# kit_calibration_VNA.net
KiCad netlist of a schematic drawn in EAGLE
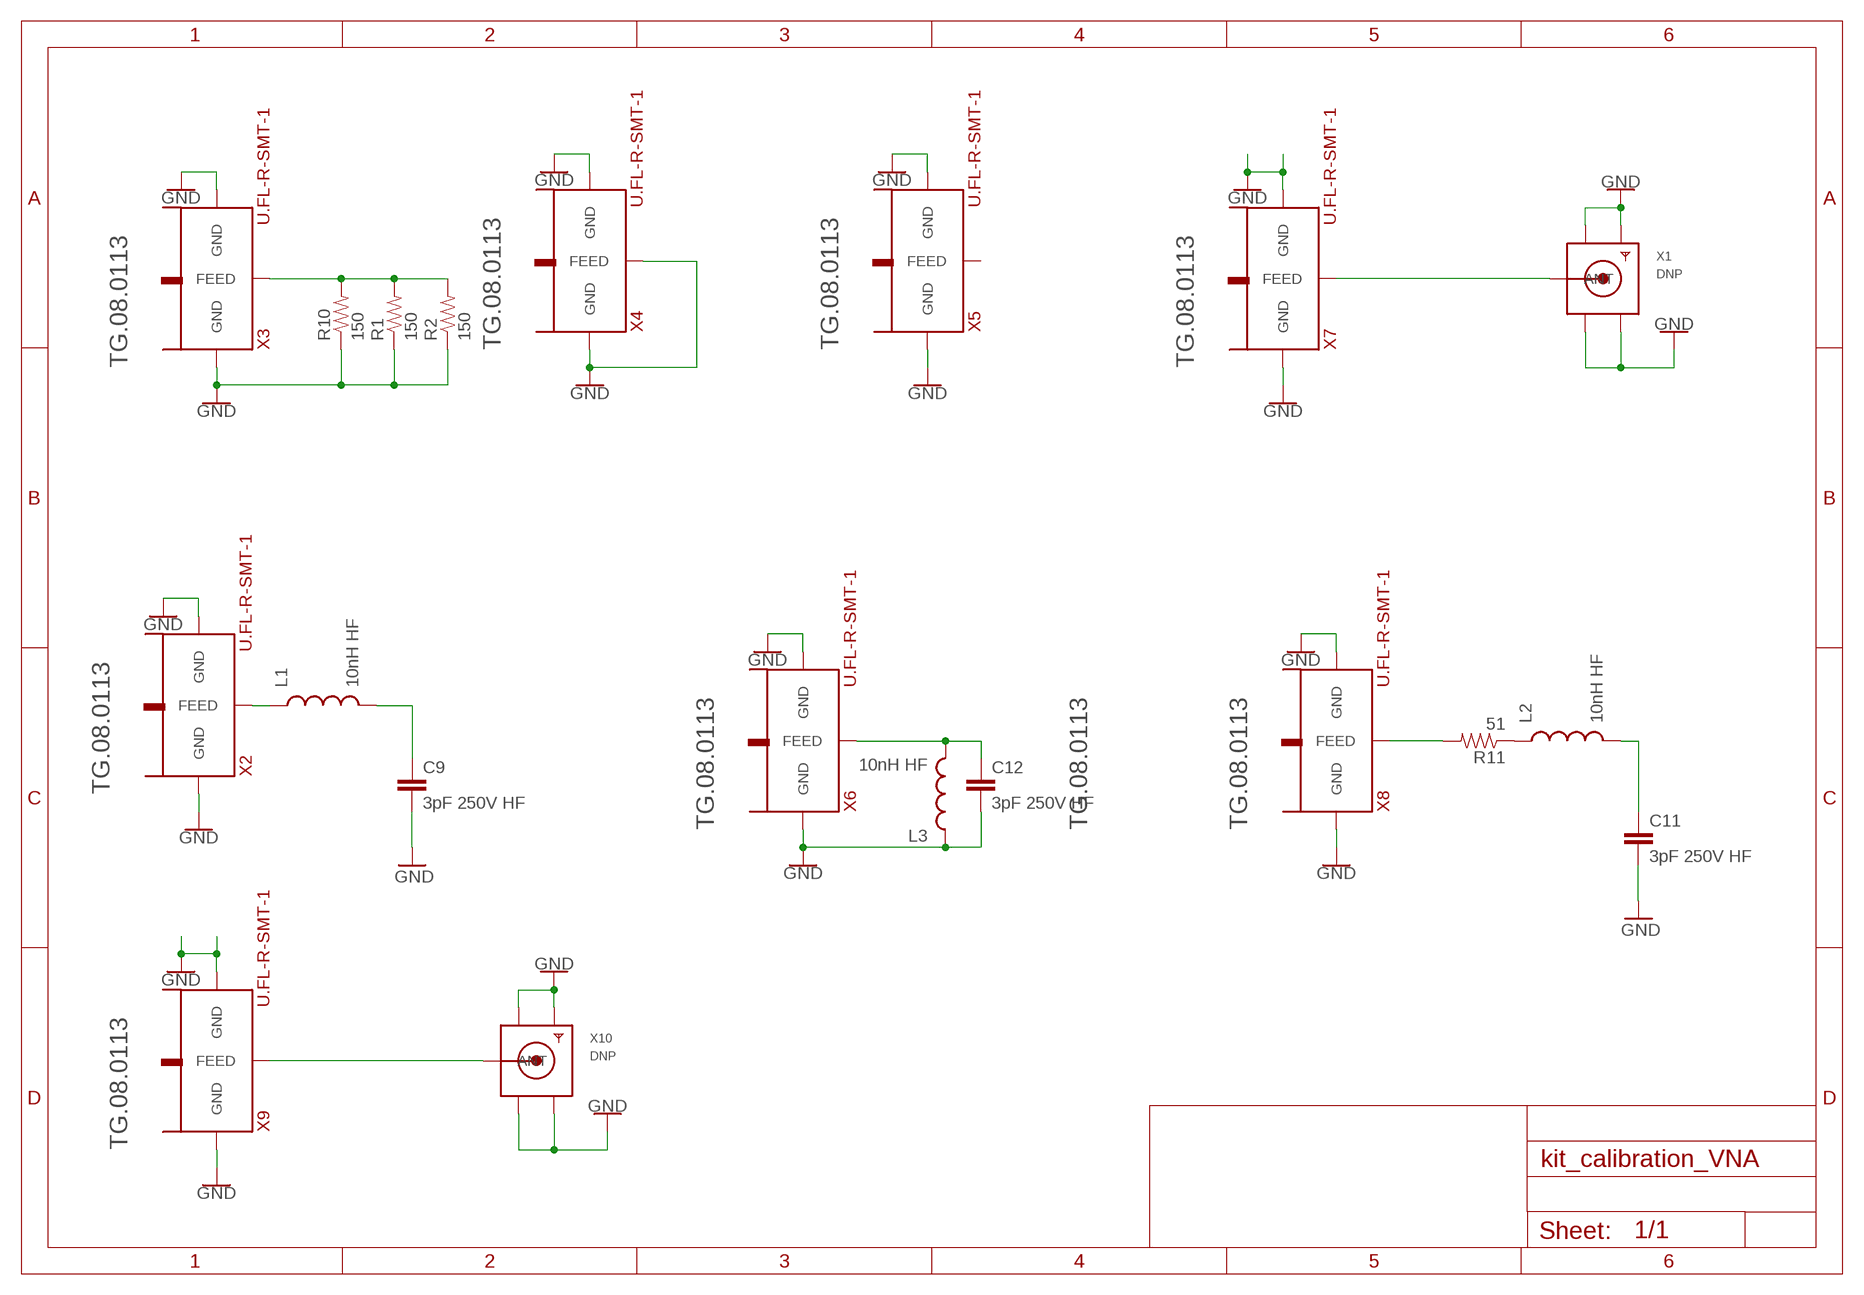
[diagram p0: schematic, sheet 1]

(export (version "E")
  (design (tool "Eeschema 10.0.6"))
  (components
    (comp (ref "C9")
      (value "3pF 250V HF")
      (footprint "eagle-import:0603-CAP")
      (libsource (lib "eagle-import") (part "CAP0603-CAP"))
    )
    (comp (ref "C11")
      (value "3pF 250V HF")
      (footprint "eagle-import:0603-CAP")
      (libsource (lib "eagle-import") (part "CAP0603-CAP"))
    )
    (comp (ref "C12")
      (value "3pF 250V HF")
      (footprint "eagle-import:0603-CAP")
      (libsource (lib "eagle-import") (part "CAP0603-CAP"))
    )
    (comp (ref "L1")
      (value "10nH HF")
      (footprint "eagle-import:0603")
      (libsource (lib "eagle-import") (part "INDUCTOR0603"))
    )
    (comp (ref "L2")
      (value "10nH HF")
      (footprint "eagle-import:0603")
      (libsource (lib "eagle-import") (part "INDUCTOR0603"))
    )
    (comp (ref "L3")
      (value "10nH HF")
      (footprint "eagle-import:0603")
      (libsource (lib "eagle-import") (part "INDUCTOR0603"))
    )
    (comp (ref "R1")
      (value "150")
      (footprint "eagle-import:0603-RES")
      (libsource (lib "eagle-import") (part "RESISTOR0603-RES"))
    )
    (comp (ref "R2")
      (value "150")
      (footprint "eagle-import:0603-RES")
      (libsource (lib "eagle-import") (part "RESISTOR0603-RES"))
    )
    (comp (ref "R10")
      (value "150")
      (footprint "eagle-import:0603-RES")
      (libsource (lib "eagle-import") (part "RESISTOR0603-RES"))
    )
    (comp (ref "R11")
      (value "51")
      (footprint "eagle-import:0603-RES")
      (libsource (lib "eagle-import") (part "RESISTOR0603-RES"))
    )
    (comp (ref "X1")
      (value "DNP")
      (footprint "eagle-import:SMA_EDGELAUNCH")
      (libsource (lib "eagle-import") (part "SMACONNECTOR_EDGE"))
    )
    (comp (ref "X2")
      (value "U.FL-R-SMT-1")
      (footprint "eagle-import:U.FL-R-SMT-1")
      (libsource (lib "eagle-import") (part "U.FL-R-SMT-1"))
    )
    (comp (ref "X3")
      (value "U.FL-R-SMT-1")
      (footprint "eagle-import:U.FL-R-SMT-1")
      (libsource (lib "eagle-import") (part "U.FL-R-SMT-1"))
    )
    (comp (ref "X4")
      (value "U.FL-R-SMT-1")
      (footprint "eagle-import:U.FL-R-SMT-1")
      (libsource (lib "eagle-import") (part "U.FL-R-SMT-1"))
    )
    (comp (ref "X5")
      (value "U.FL-R-SMT-1")
      (footprint "eagle-import:U.FL-R-SMT-1")
      (libsource (lib "eagle-import") (part "U.FL-R-SMT-1"))
    )
    (comp (ref "X6")
      (value "U.FL-R-SMT-1")
      (footprint "eagle-import:U.FL-R-SMT-1")
      (libsource (lib "eagle-import") (part "U.FL-R-SMT-1"))
    )
    (comp (ref "X7")
      (value "U.FL-R-SMT-1")
      (footprint "eagle-import:U.FL-R-SMT-1")
      (libsource (lib "eagle-import") (part "U.FL-R-SMT-1"))
    )
    (comp (ref "X8")
      (value "U.FL-R-SMT-1")
      (footprint "eagle-import:U.FL-R-SMT-1")
      (libsource (lib "eagle-import") (part "U.FL-R-SMT-1"))
    )
    (comp (ref "X9")
      (value "U.FL-R-SMT-1")
      (footprint "eagle-import:U.FL-R-SMT-1")
      (libsource (lib "eagle-import") (part "U.FL-R-SMT-1"))
    )
    (comp (ref "X10")
      (value "DNP")
      (footprint "eagle-import:SMA_EDGELAUNCH")
      (libsource (lib "eagle-import") (part "SMACONNECTOR_EDGE"))
    )
  )
  (nets
    (net (code "1") (name "GND") (class "Default")
      (node (ref "C11") (pin "2") (pinfunction "2_2") (pintype "passive"))
      (node (ref "C12") (pin "2") (pinfunction "2_2") (pintype "passive"))
      (node (ref "C9") (pin "2") (pinfunction "2_2") (pintype "passive"))
      (node (ref "L3") (pin "1") (pinfunction "1_1") (pintype "passive"))
      (node (ref "R1") (pin "1") (pinfunction "1_1") (pintype "passive"))
      (node (ref "R10") (pin "1") (pinfunction "1_1") (pintype "passive"))
      (node (ref "R2") (pin "1") (pinfunction "1_1") (pintype "passive"))
      (node (ref "X1") (pin "GND@1") (pinfunction "GND4_GND@1") (pintype "power_in"))
      (node (ref "X1") (pin "GND@2") (pinfunction "GND3_GND@2") (pintype "power_in"))
      (node (ref "X1") (pin "GND@3") (pinfunction "GND2_GND@3") (pintype "power_in"))
      (node (ref "X1") (pin "GND@4") (pinfunction "GND1_GND@4") (pintype "power_in"))
      (node (ref "X10") (pin "GND@1") (pinfunction "GND4_GND@1") (pintype "power_in"))
      (node (ref "X10") (pin "GND@2") (pinfunction "GND3_GND@2") (pintype "power_in"))
      (node (ref "X10") (pin "GND@3") (pinfunction "GND2_GND@3") (pintype "power_in"))
      (node (ref "X10") (pin "GND@4") (pinfunction "GND1_GND@4") (pintype "power_in"))
      (node (ref "X2") (pin "P$1") (pinfunction "GND_P$1") (pintype "power_in"))
      (node (ref "X2") (pin "P$2") (pinfunction "GND_P$2") (pintype "power_in"))
      (node (ref "X3") (pin "P$1") (pinfunction "GND_P$1") (pintype "power_in"))
      (node (ref "X3") (pin "P$2") (pinfunction "GND_P$2") (pintype "power_in"))
      (node (ref "X4") (pin "P$1") (pinfunction "GND_P$1") (pintype "power_in"))
      (node (ref "X4") (pin "P$2") (pinfunction "GND_P$2") (pintype "power_in"))
      (node (ref "X4") (pin "P$3") (pinfunction "FEED_P$3") (pintype "bidirectional"))
      (node (ref "X5") (pin "P$1") (pinfunction "GND_P$1") (pintype "power_in"))
      (node (ref "X5") (pin "P$2") (pinfunction "GND_P$2") (pintype "power_in"))
      (node (ref "X6") (pin "P$1") (pinfunction "GND_P$1") (pintype "power_in"))
      (node (ref "X6") (pin "P$2") (pinfunction "GND_P$2") (pintype "power_in"))
      (node (ref "X7") (pin "P$1") (pinfunction "GND_P$1") (pintype "power_in"))
      (node (ref "X7") (pin "P$2") (pinfunction "GND_P$2") (pintype "power_in"))
      (node (ref "X8") (pin "P$1") (pinfunction "GND_P$1") (pintype "power_in"))
      (node (ref "X8") (pin "P$2") (pinfunction "GND_P$2") (pintype "power_in"))
      (node (ref "X9") (pin "P$1") (pinfunction "GND_P$1") (pintype "power_in"))
      (node (ref "X9") (pin "P$2") (pinfunction "GND_P$2") (pintype "power_in"))
    )
    (net (code "2") (name "Net-(C9-Pad1)") (class "Default")
      (node (ref "C9") (pin "1") (pinfunction "1_1") (pintype "passive"))
      (node (ref "L1") (pin "2") (pinfunction "2_2") (pintype "passive"))
    )
    (net (code "3") (name "Net-(C11-Pad1)") (class "Default")
      (node (ref "C11") (pin "1") (pinfunction "1_1") (pintype "passive"))
      (node (ref "L2") (pin "2") (pinfunction "2_2") (pintype "passive"))
    )
    (net (code "4") (name "Net-(L2-Pad1)") (class "Default")
      (node (ref "L2") (pin "1") (pinfunction "1_1") (pintype "passive"))
      (node (ref "R11") (pin "1") (pinfunction "1_1") (pintype "passive"))
    )
    (net (code "5") (name "Net-(X1-ANT)") (class "Default")
      (node (ref "X1") (pin "P") (pinfunction "ANT_P") (pintype "bidirectional"))
      (node (ref "X7") (pin "P$3") (pinfunction "FEED_P$3") (pintype "bidirectional"))
    )
    (net (code "6") (name "Net-(X2-FEED)") (class "Default")
      (node (ref "L1") (pin "1") (pinfunction "1_1") (pintype "passive"))
      (node (ref "X2") (pin "P$3") (pinfunction "FEED_P$3") (pintype "bidirectional"))
    )
    (net (code "7") (name "Net-(X3-FEED)") (class "Default")
      (node (ref "R1") (pin "2") (pinfunction "2_2") (pintype "passive"))
      (node (ref "R10") (pin "2") (pinfunction "2_2") (pintype "passive"))
      (node (ref "R2") (pin "2") (pinfunction "2_2") (pintype "passive"))
      (node (ref "X3") (pin "P$3") (pinfunction "FEED_P$3") (pintype "bidirectional"))
    )
    (net (code "8") (name "Net-(X6-FEED)") (class "Default")
      (node (ref "C12") (pin "1") (pinfunction "1_1") (pintype "passive"))
      (node (ref "L3") (pin "2") (pinfunction "2_2") (pintype "passive"))
      (node (ref "X6") (pin "P$3") (pinfunction "FEED_P$3") (pintype "bidirectional"))
    )
    (net (code "9") (name "Net-(X8-FEED)") (class "Default")
      (node (ref "R11") (pin "2") (pinfunction "2_2") (pintype "passive"))
      (node (ref "X8") (pin "P$3") (pinfunction "FEED_P$3") (pintype "bidirectional"))
    )
    (net (code "10") (name "Net-(X10-ANT)") (class "Default")
      (node (ref "X10") (pin "P") (pinfunction "ANT_P") (pintype "bidirectional"))
      (node (ref "X9") (pin "P$3") (pinfunction "FEED_P$3") (pintype "bidirectional"))
    )
    (net (code "11") (name "unconnected-(X5-FEED-PadP$3)") (class "Default")
      (node (ref "X5") (pin "P$3") (pinfunction "FEED_P$3") (pintype "bidirectional"))
    )
  )
)
